# Sheet5.net
KiCad netlist of a schematic drawn in Altium Designer
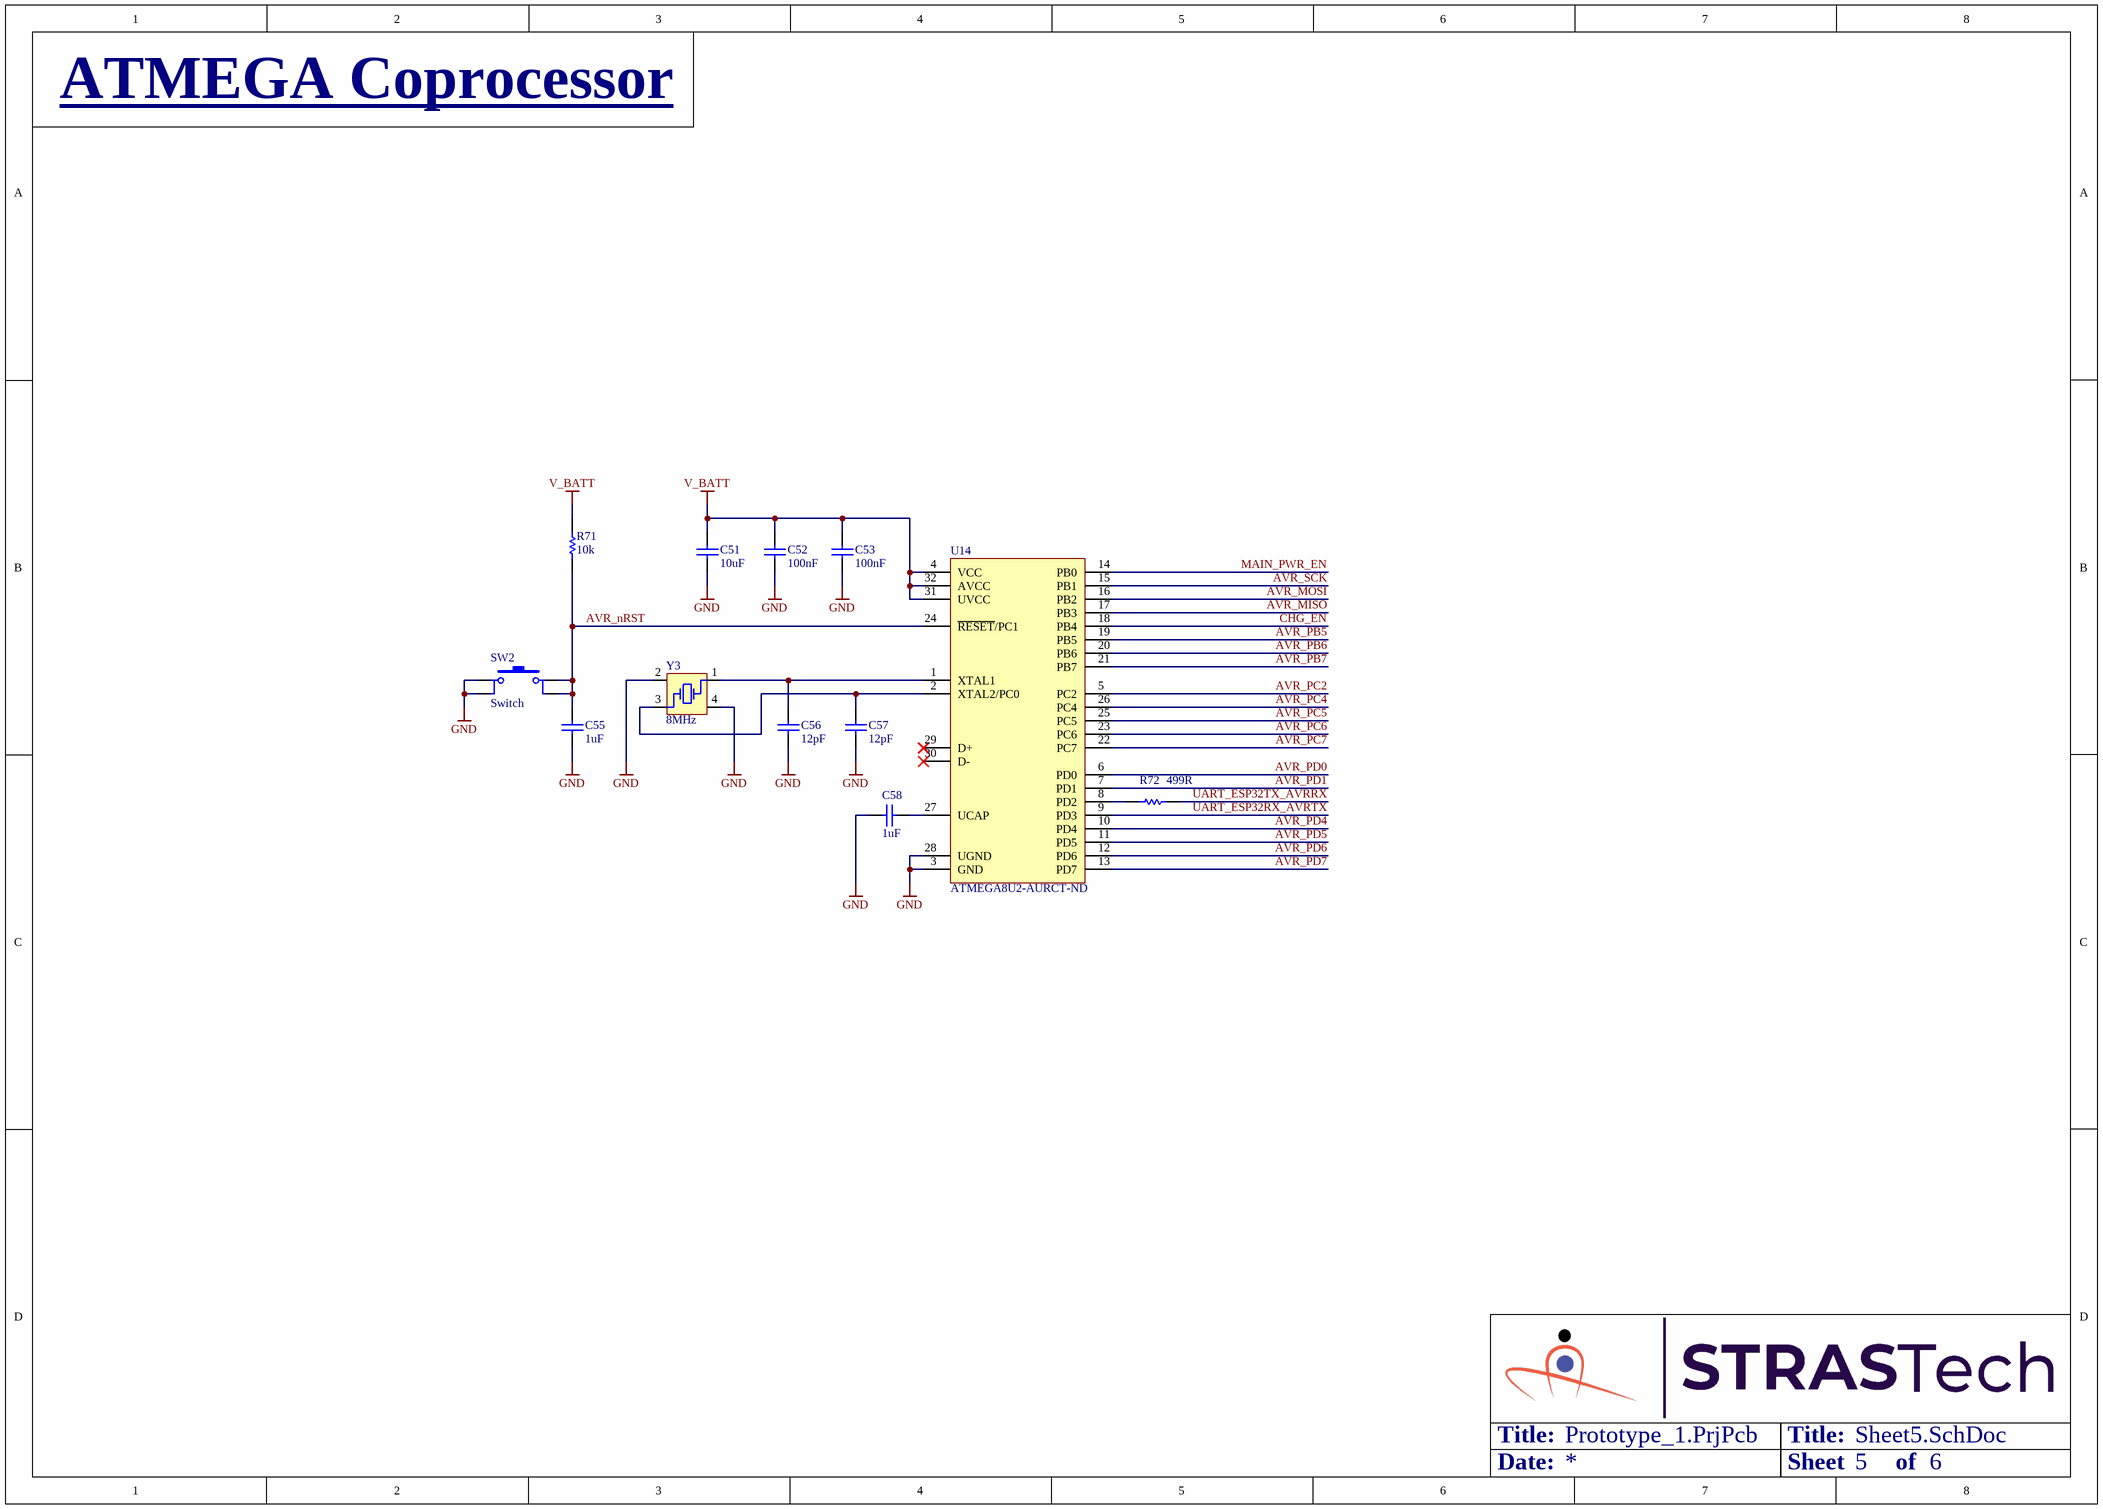
[diagram p0: Sheet5.SchDoc]

(export (version "E")
  (design (tool "Eeschema 10.0.6"))
  (components
    (comp (ref "C51")
      (value "10uF")
      (footprint "Cap,SMD,0402")
      (description "10 µF ±20% 10V Ceramic Capacitor X5R 0402 (1005 Metric)")
      (fields
        (field (name "VENDOR PART NUMBER") "1276-1450-1-ND")
        (field (name "MANUFACTURER") "Samsung Electro-Mechanics")
        (field (name "CREATEDBY") "Judd Foster")
      )
      (libsource (lib "symbols") (part "CAP,Cer,10uF,10VDC,X5R,0402"))
    )
    (comp (ref "C52")
      (value "100nF")
      (footprint "Cap,SMD,0402")
      (description "0.1µF ±10% 25V Ceramic Capacitor X7R 0402 (1005 Metric)")
      (fields
        (field (name "VENDOR PART NUMBER") "490-14603-1-ND")
        (field (name "MANUFACTURER") "Murata Electronics")
        (field (name "CREATEDBY") "Judd Foster")
      )
      (libsource (lib "symbols") (part "CAP,Cer,100nF,25VDC,X7R,0402"))
    )
    (comp (ref "C53")
      (value "100nF")
      (footprint "Cap,SMD,0402")
      (description "0.1µF ±10% 25V Ceramic Capacitor X7R 0402 (1005 Metric)")
      (fields
        (field (name "VENDOR PART NUMBER") "490-14603-1-ND")
        (field (name "MANUFACTURER") "Murata Electronics")
        (field (name "CREATEDBY") "Judd Foster")
      )
      (libsource (lib "symbols") (part "CAP,Cer,100nF,25VDC,X7R,0402"))
    )
    (comp (ref "C55")
      (value "1uF")
      (footprint "Cap,SMD,0402")
      (description "1 µF ±10% 35V Ceramic Capacitor X5R 0402 (1005 Metric)")
      (fields
        (field (name "VENDOR PART NUMBER") "445-9073-1-ND")
        (field (name "MANUFACTURER") "TDK Corporation")
        (field (name "CREATEDBY") "Judd Foster")
      )
      (libsource (lib "symbols") (part "CAP,Cer,1uF,35VDC,X5R,0402"))
    )
    (comp (ref "C56")
      (value "12pF")
      (footprint "Cap,SMD,0402")
      (description "12pF ±5% 50V Ceramic Capacitor C0G, NP0 0402 (1005 Metric)")
      (fields
        (field (name "VENDOR PART NUMBER") "311-1016-1-ND")
        (field (name "MANUFACTURER") "Yageo")
        (field (name "CREATEDBY") "Judd Foster")
      )
      (libsource (lib "symbols") (part "CAP,Cer,12pF,50VDC,C0G/NP0,0402"))
    )
    (comp (ref "C57")
      (value "12pF")
      (footprint "Cap,SMD,0402")
      (description "12pF ±5% 50V Ceramic Capacitor C0G, NP0 0402 (1005 Metric)")
      (fields
        (field (name "VENDOR PART NUMBER") "311-1016-1-ND")
        (field (name "MANUFACTURER") "Yageo")
        (field (name "CREATEDBY") "Judd Foster")
      )
      (libsource (lib "symbols") (part "CAP,Cer,12pF,50VDC,C0G/NP0,0402"))
    )
    (comp (ref "C58")
      (value "1uF")
      (footprint "Cap,SMD,0402")
      (description "1 µF ±10% 35V Ceramic Capacitor X5R 0402 (1005 Metric)")
      (fields
        (field (name "VENDOR PART NUMBER") "445-9073-1-ND")
        (field (name "MANUFACTURER") "TDK Corporation")
        (field (name "CREATEDBY") "Judd Foster")
      )
      (libsource (lib "symbols") (part "CAP,Cer,1uF,35VDC,X5R,0402"))
    )
    (comp (ref "R71")
      (value "10k")
      (footprint "RES,0402")
      (description "10 kOhms ±5% 0.063W, 1/16W Chip Resistor 0402 (1005 Metric) Automotive AEC-Q200 Thick Film")
      (fields
        (field (name "VENDOR PART NUMBER") "RMCF0402JT10K0CT-ND")
        (field (name "MANUFACTURER") "Stackpole Electronics Inc")
        (field (name "CREATEDBY") "Judd Foster")
      )
      (libsource (lib "symbols") (part "RES,10k,5%,0.063W,0402"))
    )
    (comp (ref "R72")
      (value "499R")
      (footprint "RES,0402")
      (description "499 Ohms ±1% 0.063W, 1/16W Chip Resistor 0402 (1005 Metric) Automotive AEC-Q200 Thick Film")
      (fields
        (field (name "MANUFACTURER") "Stackpole Electronics Inc")
        (field (name "MANUFACTURER PART NUMBER") "RMCF0402FT499R")
        (field (name "CREATEDBY") "Judd Foster")
      )
      (libsource (lib "symbols") (part "RES,499R,1%,0.063W,0402"))
    )
    (comp (ref "SW2")
      (value "Switch")
      (footprint "Switch,Tactile,Micro,SPST-NO,SMD")
      (description "Tactile Switch SPST-NO Top Actuated Surface Mount")
      (fields
        (field (name "MANUFACTURER") "C&K")
        (field (name "MANUFACTURER PART NUMBER") "PTS525SM15SMTR2 LFS")
        (field (name "CREATEDBY") "Judd Foster")
      )
      (libsource (lib "symbols") (part "Switch,Tactile,SPST-NO,SMD,H1.5"))
    )
    (comp (ref "U14")
      (value "ATMEGA8U2-AURCT-ND")
      (footprint "IC,TQFP-32,7x7,P0.8MM")
      (description "AVR series Microcontroller IC 8-Bit 16MHz 8KB (4K x 16) FLASH 32-TQFP (7x7)")
      (fields
        (field (name "MANUFACTURER PART NUMBER") "ATMEGA8U2-AUR")
        (field (name "MANUFACTURER") "Microchip Technology")
        (field (name "CREATEDBY") "Judd Foster")
      )
      (libsource (lib "symbols") (part "ATMEGA8U2-AURCT-ND"))
    )
    (comp (ref "Y3")
      (value "8MHz")
      (footprint "XTAL,SMD,4 Pin")
      (description "8 MHz ±20ppm Crystal 12pF 400 Ohms 4-SMD, No Lead")
      (fields
        (field (name "MANUFACTURER") "ECS Inc.")
        (field (name "MANUFACTURER PART NUMBER") "ECS-80-12-33-JGN-TR")
        (field (name "CREATEDBY") "Judd Foster")
      )
      (libsource (lib "symbols") (part "XTAL,8MHz,12pF,SMD"))
    )
  )
  (nets
    (net (code "1") (name "/AVR_MISO") (class "Default")
      (node (ref "U14") (pin "17") (pinfunction "PB3_17") (pintype "passive"))
    )
    (net (code "2") (name "/AVR_MOSI") (class "Default")
      (node (ref "U14") (pin "16") (pinfunction "PB2_16") (pintype "passive"))
    )
    (net (code "3") (name "/AVR_PB5") (class "Default")
      (node (ref "U14") (pin "19") (pinfunction "PB5_19") (pintype "passive"))
    )
    (net (code "4") (name "/AVR_PB6") (class "Default")
      (node (ref "U14") (pin "20") (pinfunction "PB6_20") (pintype "passive"))
    )
    (net (code "5") (name "/AVR_PB7") (class "Default")
      (node (ref "U14") (pin "21") (pinfunction "PB7_21") (pintype "passive"))
    )
    (net (code "6") (name "/AVR_PC2") (class "Default")
      (node (ref "U14") (pin "5") (pinfunction "PC2_5") (pintype "passive"))
    )
    (net (code "7") (name "/AVR_PC4") (class "Default")
      (node (ref "U14") (pin "26") (pinfunction "PC4_26") (pintype "passive"))
    )
    (net (code "8") (name "/AVR_PC5") (class "Default")
      (node (ref "U14") (pin "25") (pinfunction "PC5_25") (pintype "passive"))
    )
    (net (code "9") (name "/AVR_PC6") (class "Default")
      (node (ref "U14") (pin "23") (pinfunction "PC6_23") (pintype "passive"))
    )
    (net (code "10") (name "/AVR_PC7") (class "Default")
      (node (ref "U14") (pin "22") (pinfunction "PC7_22") (pintype "passive"))
    )
    (net (code "11") (name "/AVR_PD0") (class "Default")
      (node (ref "U14") (pin "6") (pinfunction "PD0_6") (pintype "passive"))
    )
    (net (code "12") (name "/AVR_PD1") (class "Default")
      (node (ref "U14") (pin "7") (pinfunction "PD1_7") (pintype "passive"))
    )
    (net (code "13") (name "/AVR_PD4") (class "Default")
      (node (ref "U14") (pin "10") (pinfunction "PD4_10") (pintype "passive"))
    )
    (net (code "14") (name "/AVR_PD5") (class "Default")
      (node (ref "U14") (pin "11") (pinfunction "PD5_11") (pintype "passive"))
    )
    (net (code "15") (name "/AVR_PD6") (class "Default")
      (node (ref "U14") (pin "12") (pinfunction "PD6_12") (pintype "passive"))
    )
    (net (code "16") (name "/AVR_PD7") (class "Default")
      (node (ref "U14") (pin "13") (pinfunction "PD7_13") (pintype "passive"))
    )
    (net (code "17") (name "/AVR_SCK") (class "Default")
      (node (ref "U14") (pin "15") (pinfunction "PB1_15") (pintype "passive"))
    )
    (net (code "18") (name "/AVR_nRST") (class "Default")
      (node (ref "C55") (pin "1") (pinfunction "1_1") (pintype "passive"))
      (node (ref "R71") (pin "2") (pinfunction "2_2") (pintype "passive"))
      (node (ref "SW2") (pin "3") (pinfunction "3_3") (pintype "passive"))
      (node (ref "SW2") (pin "4") (pinfunction "4_4") (pintype "passive"))
      (node (ref "U14") (pin "24") (pinfunction "~{RESET}/PC1_24") (pintype "passive"))
    )
    (net (code "19") (name "/CHG_EN") (class "Default")
      (node (ref "U14") (pin "18") (pinfunction "PB4_18") (pintype "passive"))
    )
    (net (code "20") (name "/MAIN_PWR_EN") (class "Default")
      (node (ref "U14") (pin "14") (pinfunction "PB0_14") (pintype "passive"))
    )
    (net (code "21") (name "/UART_ESP32RX_AVRTX") (class "Default")
      (node (ref "U14") (pin "9") (pinfunction "PD3_9") (pintype "passive"))
    )
    (net (code "22") (name "/UART_ESP32TX_AVRRX") (class "Default")
      (node (ref "R72") (pin "2") (pinfunction "2_2") (pintype "passive"))
    )
    (net (code "23") (name "GND") (class "Default")
      (node (ref "C51") (pin "1") (pinfunction "1_1") (pintype "passive"))
      (node (ref "C52") (pin "1") (pinfunction "1_1") (pintype "passive"))
      (node (ref "C53") (pin "1") (pinfunction "1_1") (pintype "passive"))
      (node (ref "C55") (pin "2") (pinfunction "2_2") (pintype "passive"))
      (node (ref "C56") (pin "2") (pinfunction "2_2") (pintype "passive"))
      (node (ref "C57") (pin "2") (pinfunction "2_2") (pintype "passive"))
      (node (ref "C58") (pin "1") (pinfunction "1_1") (pintype "passive"))
      (node (ref "SW2") (pin "1") (pinfunction "1_1") (pintype "passive"))
      (node (ref "SW2") (pin "2") (pinfunction "2_2") (pintype "passive"))
      (node (ref "U14") (pin "28") (pinfunction "UGND_28") (pintype "passive"))
      (node (ref "U14") (pin "3") (pinfunction "GND_3") (pintype "passive"))
      (node (ref "Y3") (pin "2") (pinfunction "GND_2") (pintype "passive"))
      (node (ref "Y3") (pin "4") (pinfunction "GND_4") (pintype "passive"))
    )
    (net (code "24") (name "Net-(U14-PD2)") (class "Default")
      (node (ref "R72") (pin "1") (pinfunction "1_1") (pintype "passive"))
      (node (ref "U14") (pin "8") (pinfunction "PD2_8") (pintype "passive"))
    )
    (net (code "25") (name "Net-(U14-UCAP)") (class "Default")
      (node (ref "C58") (pin "2") (pinfunction "2_2") (pintype "passive"))
      (node (ref "U14") (pin "27") (pinfunction "UCAP_27") (pintype "passive"))
    )
    (net (code "26") (name "Net-(U14-XTAL1)") (class "Default")
      (node (ref "C56") (pin "1") (pinfunction "1_1") (pintype "passive"))
      (node (ref "U14") (pin "1") (pinfunction "XTAL1_1") (pintype "passive"))
      (node (ref "Y3") (pin "1") (pinfunction "OSC1_1") (pintype "passive"))
    )
    (net (code "27") (name "Net-(U14-XTAL2{slash}PC0)") (class "Default")
      (node (ref "C57") (pin "1") (pinfunction "1_1") (pintype "passive"))
      (node (ref "U14") (pin "2") (pinfunction "XTAL2/PC0_2") (pintype "passive"))
      (node (ref "Y3") (pin "3") (pinfunction "OSC2_3") (pintype "passive"))
    )
    (net (code "28") (name "V_BATT") (class "Default")
      (node (ref "C51") (pin "2") (pinfunction "2_2") (pintype "passive"))
      (node (ref "C52") (pin "2") (pinfunction "2_2") (pintype "passive"))
      (node (ref "C53") (pin "2") (pinfunction "2_2") (pintype "passive"))
      (node (ref "R71") (pin "1") (pinfunction "1_1") (pintype "passive"))
      (node (ref "U14") (pin "31") (pinfunction "UVCC_31") (pintype "passive"))
      (node (ref "U14") (pin "32") (pinfunction "AVCC_32") (pintype "passive"))
      (node (ref "U14") (pin "4") (pinfunction "VCC_4") (pintype "passive"))
    )
    (net (code "29") (name "unconnected-(U14-D+-Pad29)") (class "Default")
      (node (ref "U14") (pin "29") (pinfunction "D+_29") (pintype "passive+no_connect"))
    )
    (net (code "30") (name "unconnected-(U14-D--Pad30)") (class "Default")
      (node (ref "U14") (pin "30") (pinfunction "D-_30") (pintype "passive+no_connect"))
    )
  )
)
